# 02-USER_IO_STATUS.net
KiCad netlist of a schematic drawn in Altium Designer
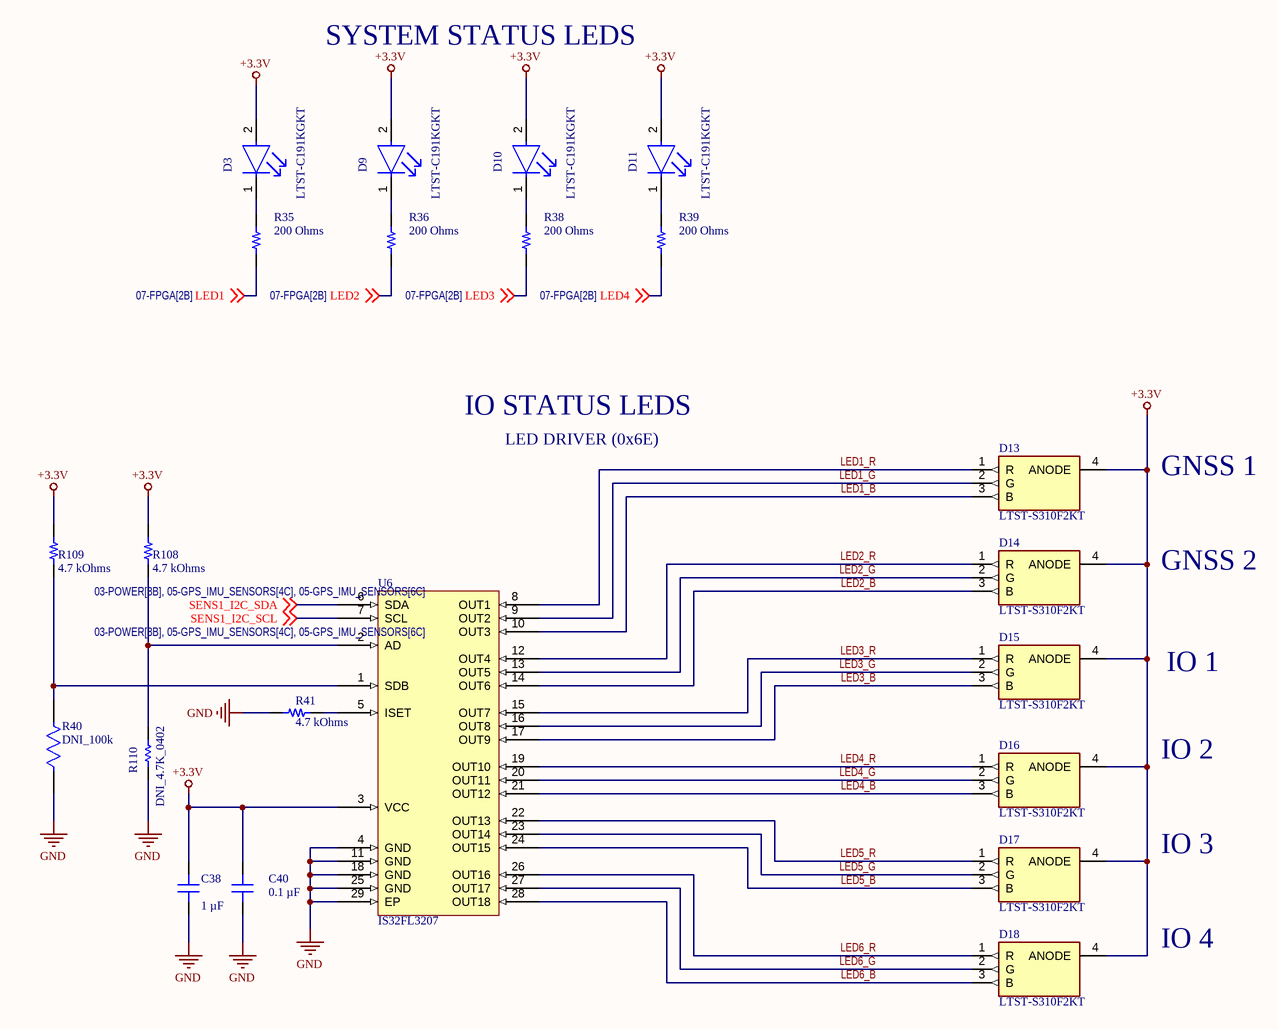
[diagram p0: 02-USER_IO_STATUS.SchDoc]

(export (version "E")
  (design (tool "Eeschema 10.0.6"))
  (components
    (comp (ref "C38")
      (value "1 µF")
      (footprint "CAP 0402_1005")
      (description "CAP CER 1UF 25V X5R 0402")
      (fields (field (name "TOLERANCE") "±10%") (field (name "PART NUMBER") "CC0402KRX5R8BB105"))
      (libsource (lib "Celestial Altium Library - altium_library") (part "Capacitor"))
    )
    (comp (ref "C40")
      (value "0.1 µF")
      (footprint "CAP 0402_1005")
      (description "CAP CER 0.1UF 50V X7R 0402")
      (fields (field (name "MANUFACTURER") "Yageo") (field (name "PART NUMBER") "CC0402KRX7R9BB104"))
      (libsource (lib "Celestial Altium Library - altium_library") (part "Capacitor"))
    )
    (comp (ref "D3")
      (value "LTST-C191KGKT")
      (footprint "FP-LTST-C191KGKT-MFG")
      (description "LED GREEN CLEAR SMD")
      (libsource (lib "Altium Content Vault") (part "8706943c75ba83719d021d2fdc84c58"))
    )
    (comp (ref "D9")
      (value "LTST-C191KGKT")
      (footprint "FP-LTST-C191KGKT-MFG")
      (description "LED GREEN CLEAR SMD")
      (libsource (lib "Altium Content Vault") (part "8706943c75ba83719d021d2fdc84c58"))
    )
    (comp (ref "D10")
      (value "LTST-C191KGKT")
      (footprint "FP-LTST-C191KGKT-MFG")
      (description "LED GREEN CLEAR SMD")
      (libsource (lib "Altium Content Vault") (part "8706943c75ba83719d021d2fdc84c58"))
    )
    (comp (ref "D11")
      (value "LTST-C191KGKT")
      (footprint "FP-LTST-C191KGKT-MFG")
      (description "LED GREEN CLEAR SMD")
      (libsource (lib "Altium Content Vault") (part "8706943c75ba83719d021d2fdc84c58"))
    )
    (comp (ref "D13")
      (value "LTST-S310F2KT")
      (footprint "SamacSys:LTST-310F2KT")
      (description "LED (Multiple), RGB")
      (libsource (lib "SamacSys") (part "LTST-S310F2KT"))
    )
    (comp (ref "D14")
      (value "LTST-S310F2KT")
      (footprint "SamacSys:LTST-310F2KT")
      (description "LED (Multiple), RGB")
      (libsource (lib "SamacSys") (part "LTST-S310F2KT"))
    )
    (comp (ref "D15")
      (value "LTST-S310F2KT")
      (footprint "SamacSys:LTST-310F2KT")
      (description "LED (Multiple), RGB")
      (libsource (lib "SamacSys") (part "LTST-S310F2KT"))
    )
    (comp (ref "D16")
      (value "LTST-S310F2KT")
      (footprint "SamacSys:LTST-310F2KT")
      (description "LED (Multiple), RGB")
      (libsource (lib "SamacSys") (part "LTST-S310F2KT"))
    )
    (comp (ref "D17")
      (value "LTST-S310F2KT")
      (footprint "SamacSys:LTST-310F2KT")
      (description "LED (Multiple), RGB")
      (libsource (lib "SamacSys") (part "LTST-S310F2KT"))
    )
    (comp (ref "D18")
      (value "LTST-S310F2KT")
      (footprint "SamacSys:LTST-310F2KT")
      (description "LED (Multiple), RGB")
      (libsource (lib "SamacSys") (part "LTST-S310F2KT"))
    )
    (comp (ref "R35")
      (value "200 Ohms")
      (footprint "YAGEO RES 0402_1005")
      (description "RES 200 OHM 1% 1/16W 0402")
      (fields (field (name "MANUFACTURER") "Yageo") (field (name "PART NUMBER") "RC0402FR-07200RL"))
      (libsource (lib "Celestial Altium Library - altium_library") (part "Resistor"))
    )
    (comp (ref "R36")
      (value "200 Ohms")
      (footprint "YAGEO RES 0402_1005")
      (description "RES 200 OHM 1% 1/16W 0402")
      (fields (field (name "MANUFACTURER") "Yageo") (field (name "PART NUMBER") "RC0402FR-07200RL"))
      (libsource (lib "Celestial Altium Library - altium_library") (part "Resistor"))
    )
    (comp (ref "R38")
      (value "200 Ohms")
      (footprint "YAGEO RES 0402_1005")
      (description "RES 200 OHM 1% 1/16W 0402")
      (fields (field (name "MANUFACTURER") "Yageo") (field (name "PART NUMBER") "RC0402FR-07200RL"))
      (libsource (lib "Celestial Altium Library - altium_library") (part "Resistor"))
    )
    (comp (ref "R39")
      (value "200 Ohms")
      (footprint "YAGEO RES 0402_1005")
      (description "RES 200 OHM 1% 1/16W 0402")
      (fields (field (name "MANUFACTURER") "Yageo") (field (name "PART NUMBER") "RC0402FR-07200RL"))
      (libsource (lib "Celestial Altium Library - altium_library") (part "Resistor"))
    )
    (comp (ref "R40")
      (value "DNI_100k")
      (footprint "FP-RC0603-0_55-MFG")
      (description "RES SMD 100K OHM 1% 1/10W 0603")
      (fields (field (name "TOLERANCE") "1%"))
      (libsource (lib "Altium Content Vault") (part "1029c3af85768c4190bb7ad29bc67b5"))
    )
    (comp (ref "R41")
      (value "4.7 kOhms")
      (footprint "YAGEO RES 0402_1005")
      (description "RES 4.7K OHM 1% 1/16W 0402")
      (fields (field (name "TOLERANCE") "±1%") (field (name "PART NUMBER") "RC0402FR-074K7L"))
      (libsource (lib "Celestial Altium Library - altium_library") (part "Resistor"))
    )
    (comp (ref "R108")
      (value "4.7 kOhms")
      (footprint "YAGEO RES 0402_1005")
      (description "RES 4.7K OHM 1% 1/16W 0402")
      (fields (field (name "TOLERANCE") "±1%") (field (name "PART NUMBER") "RC0402FR-074K7L"))
      (libsource (lib "Celestial Altium Library - altium_library") (part "Resistor"))
    )
    (comp (ref "R109")
      (value "4.7 kOhms")
      (footprint "YAGEO RES 0402_1005")
      (description "RES 4.7K OHM 1% 1/16W 0402")
      (fields (field (name "TOLERANCE") "±1%") (field (name "PART NUMBER") "RC0402FR-074K7L"))
      (libsource (lib "Celestial Altium Library - altium_library") (part "Resistor"))
    )
    (comp (ref "R110")
      (value "DNI_4.7K_0402")
      (footprint "RESC1005X40X25LL05T05")
      (description "Chip Resistor, 4.7 KOhm, +/- 1%, 0.1 W, -55 to 155 degC, 0402 (1005 Metric), RoHS, Tape and Reel")
      (fields (field (name "TOLERANCE") "1%") (field (name "PARTNUMBER") "ERJ-2RKF4701X"))
      (libsource (lib "Altium Content Vault") (part "RES-2"))
    )
    (comp (ref "U6")
      (value "IS32FL3207")
      (footprint "IS32FL3207")
      (libsource (lib "IS32FL3207") (part "IS32FL3207"))
    )
  )
  (nets
    (net (code "1") (name "+3.3V") (class "Default")
      (node (ref "C38") (pin "2") (pinfunction "2_2") (pintype "passive"))
      (node (ref "C40") (pin "2") (pinfunction "2_2") (pintype "passive"))
      (node (ref "D10") (pin "2") (pinfunction "A_2") (pintype "passive"))
      (node (ref "D11") (pin "2") (pinfunction "A_2") (pintype "passive"))
      (node (ref "D13") (pin "4") (pinfunction "ANODE_4") (pintype "power_in"))
      (node (ref "D14") (pin "4") (pinfunction "ANODE_4") (pintype "power_in"))
      (node (ref "D15") (pin "4") (pinfunction "ANODE_4") (pintype "power_in"))
      (node (ref "D16") (pin "4") (pinfunction "ANODE_4") (pintype "power_in"))
      (node (ref "D17") (pin "4") (pinfunction "ANODE_4") (pintype "power_in"))
      (node (ref "D18") (pin "4") (pinfunction "ANODE_4") (pintype "power_in"))
      (node (ref "D3") (pin "2") (pinfunction "A_2") (pintype "passive"))
      (node (ref "D9") (pin "2") (pinfunction "A_2") (pintype "passive"))
      (node (ref "R108") (pin "1") (pinfunction "1_1") (pintype "passive"))
      (node (ref "R109") (pin "1") (pinfunction "1_1") (pintype "passive"))
      (node (ref "U6") (pin "3") (pinfunction "VCC_3") (pintype "input"))
    )
    (net (code "2") (name "/LED1_B") (class "Default")
      (node (ref "D13") (pin "3") (pinfunction "B_3") (pintype "output"))
      (node (ref "U6") (pin "10") (pinfunction "OUT3_10") (pintype "input"))
    )
    (net (code "3") (name "/LED1_G") (class "Default")
      (node (ref "D13") (pin "2") (pinfunction "G_2") (pintype "output"))
      (node (ref "U6") (pin "9") (pinfunction "OUT2_9") (pintype "input"))
    )
    (net (code "4") (name "/LED1_R") (class "Default")
      (node (ref "D13") (pin "1") (pinfunction "R_1") (pintype "output"))
      (node (ref "U6") (pin "8") (pinfunction "OUT1_8") (pintype "input"))
    )
    (net (code "5") (name "/LED2_B") (class "Default")
      (node (ref "D14") (pin "3") (pinfunction "B_3") (pintype "output"))
      (node (ref "U6") (pin "14") (pinfunction "OUT6_14") (pintype "input"))
    )
    (net (code "6") (name "/LED2_G") (class "Default")
      (node (ref "D14") (pin "2") (pinfunction "G_2") (pintype "output"))
      (node (ref "U6") (pin "13") (pinfunction "OUT5_13") (pintype "input"))
    )
    (net (code "7") (name "/LED2_R") (class "Default")
      (node (ref "D14") (pin "1") (pinfunction "R_1") (pintype "output"))
      (node (ref "U6") (pin "12") (pinfunction "OUT4_12") (pintype "input"))
    )
    (net (code "8") (name "/LED3_B") (class "Default")
      (node (ref "D15") (pin "3") (pinfunction "B_3") (pintype "output"))
      (node (ref "U6") (pin "17") (pinfunction "OUT9_17") (pintype "input"))
    )
    (net (code "9") (name "/LED3_G") (class "Default")
      (node (ref "D15") (pin "2") (pinfunction "G_2") (pintype "output"))
      (node (ref "U6") (pin "16") (pinfunction "OUT8_16") (pintype "input"))
    )
    (net (code "10") (name "/LED3_R") (class "Default")
      (node (ref "D15") (pin "1") (pinfunction "R_1") (pintype "output"))
      (node (ref "U6") (pin "15") (pinfunction "OUT7_15") (pintype "input"))
    )
    (net (code "11") (name "/LED4_B") (class "Default")
      (node (ref "D16") (pin "3") (pinfunction "B_3") (pintype "output"))
      (node (ref "U6") (pin "21") (pinfunction "OUT12_21") (pintype "input"))
    )
    (net (code "12") (name "/LED4_G") (class "Default")
      (node (ref "D16") (pin "2") (pinfunction "G_2") (pintype "output"))
      (node (ref "U6") (pin "20") (pinfunction "OUT11_20") (pintype "input"))
    )
    (net (code "13") (name "/LED4_R") (class "Default")
      (node (ref "D16") (pin "1") (pinfunction "R_1") (pintype "output"))
      (node (ref "U6") (pin "19") (pinfunction "OUT10_19") (pintype "input"))
    )
    (net (code "14") (name "/LED5_B") (class "Default")
      (node (ref "D17") (pin "3") (pinfunction "B_3") (pintype "output"))
      (node (ref "U6") (pin "24") (pinfunction "OUT15_24") (pintype "input"))
    )
    (net (code "15") (name "/LED5_G") (class "Default")
      (node (ref "D17") (pin "2") (pinfunction "G_2") (pintype "output"))
      (node (ref "U6") (pin "23") (pinfunction "OUT14_23") (pintype "input"))
    )
    (net (code "16") (name "/LED5_R") (class "Default")
      (node (ref "D17") (pin "1") (pinfunction "R_1") (pintype "output"))
      (node (ref "U6") (pin "22") (pinfunction "OUT13_22") (pintype "input"))
    )
    (net (code "17") (name "/LED6_B") (class "Default")
      (node (ref "D18") (pin "3") (pinfunction "B_3") (pintype "output"))
      (node (ref "U6") (pin "28") (pinfunction "OUT18_28") (pintype "input"))
    )
    (net (code "18") (name "/LED6_G") (class "Default")
      (node (ref "D18") (pin "2") (pinfunction "G_2") (pintype "output"))
      (node (ref "U6") (pin "27") (pinfunction "OUT17_27") (pintype "input"))
    )
    (net (code "19") (name "/LED6_R") (class "Default")
      (node (ref "D18") (pin "1") (pinfunction "R_1") (pintype "output"))
      (node (ref "U6") (pin "26") (pinfunction "OUT16_26") (pintype "input"))
    )
    (net (code "20") (name "GND") (class "Default")
      (node (ref "C38") (pin "1") (pinfunction "1_1") (pintype "passive"))
      (node (ref "C40") (pin "1") (pinfunction "1_1") (pintype "passive"))
      (node (ref "R110") (pin "2") (pinfunction "2_2") (pintype "passive"))
      (node (ref "R40") (pin "1") (pinfunction "1_1") (pintype "passive"))
      (node (ref "R41") (pin "1") (pinfunction "1_1") (pintype "passive"))
      (node (ref "U6") (pin "11") (pinfunction "GND_11") (pintype "input"))
      (node (ref "U6") (pin "18") (pinfunction "GND_18") (pintype "input"))
      (node (ref "U6") (pin "25") (pinfunction "GND_25") (pintype "input"))
      (node (ref "U6") (pin "29") (pinfunction "EP_29") (pintype "input"))
      (node (ref "U6") (pin "4") (pinfunction "GND_4") (pintype "input"))
    )
    (net (code "21") (name "LED1") (class "Default")
      (node (ref "R35") (pin "1") (pinfunction "1_1") (pintype "passive"))
    )
    (net (code "22") (name "LED2") (class "Default")
      (node (ref "R36") (pin "1") (pinfunction "1_1") (pintype "passive"))
    )
    (net (code "23") (name "LED3") (class "Default")
      (node (ref "R38") (pin "1") (pinfunction "1_1") (pintype "passive"))
    )
    (net (code "24") (name "LED4") (class "Default")
      (node (ref "R39") (pin "1") (pinfunction "1_1") (pintype "passive"))
    )
    (net (code "25") (name "Net-(D3-C)") (class "Default")
      (node (ref "D3") (pin "1") (pinfunction "C_1") (pintype "passive"))
      (node (ref "R35") (pin "2") (pinfunction "2_2") (pintype "passive"))
    )
    (net (code "26") (name "Net-(D9-C)") (class "Default")
      (node (ref "D9") (pin "1") (pinfunction "C_1") (pintype "passive"))
      (node (ref "R36") (pin "2") (pinfunction "2_2") (pintype "passive"))
    )
    (net (code "27") (name "Net-(D10-C)") (class "Default")
      (node (ref "D10") (pin "1") (pinfunction "C_1") (pintype "passive"))
      (node (ref "R38") (pin "2") (pinfunction "2_2") (pintype "passive"))
    )
    (net (code "28") (name "Net-(D11-C)") (class "Default")
      (node (ref "D11") (pin "1") (pinfunction "C_1") (pintype "passive"))
      (node (ref "R39") (pin "2") (pinfunction "2_2") (pintype "passive"))
    )
    (net (code "29") (name "Net-(U6-AD)") (class "Default")
      (node (ref "R108") (pin "2") (pinfunction "2_2") (pintype "passive"))
      (node (ref "R110") (pin "1") (pinfunction "1_1") (pintype "passive"))
      (node (ref "U6") (pin "2") (pinfunction "AD_2") (pintype "input"))
    )
    (net (code "30") (name "Net-(U6-ISET)") (class "Default")
      (node (ref "R41") (pin "2") (pinfunction "2_2") (pintype "passive"))
      (node (ref "U6") (pin "5") (pinfunction "ISET_5") (pintype "input"))
    )
    (net (code "31") (name "Net-(U6-SDB)") (class "Default")
      (node (ref "R109") (pin "2") (pinfunction "2_2") (pintype "passive"))
      (node (ref "R40") (pin "2") (pinfunction "2_2") (pintype "passive"))
      (node (ref "U6") (pin "1") (pinfunction "SDB_1") (pintype "input"))
    )
    (net (code "32") (name "SENS1_I2C_SCL") (class "Default")
      (node (ref "U6") (pin "7") (pinfunction "SCL_7") (pintype "input"))
    )
    (net (code "33") (name "SENS1_I2C_SDA") (class "Default")
      (node (ref "U6") (pin "6") (pinfunction "SDA_6") (pintype "input"))
    )
  )
)
